# M3_SN755410_1_2.net
KiCad netlist of a schematic drawn in EAGLE
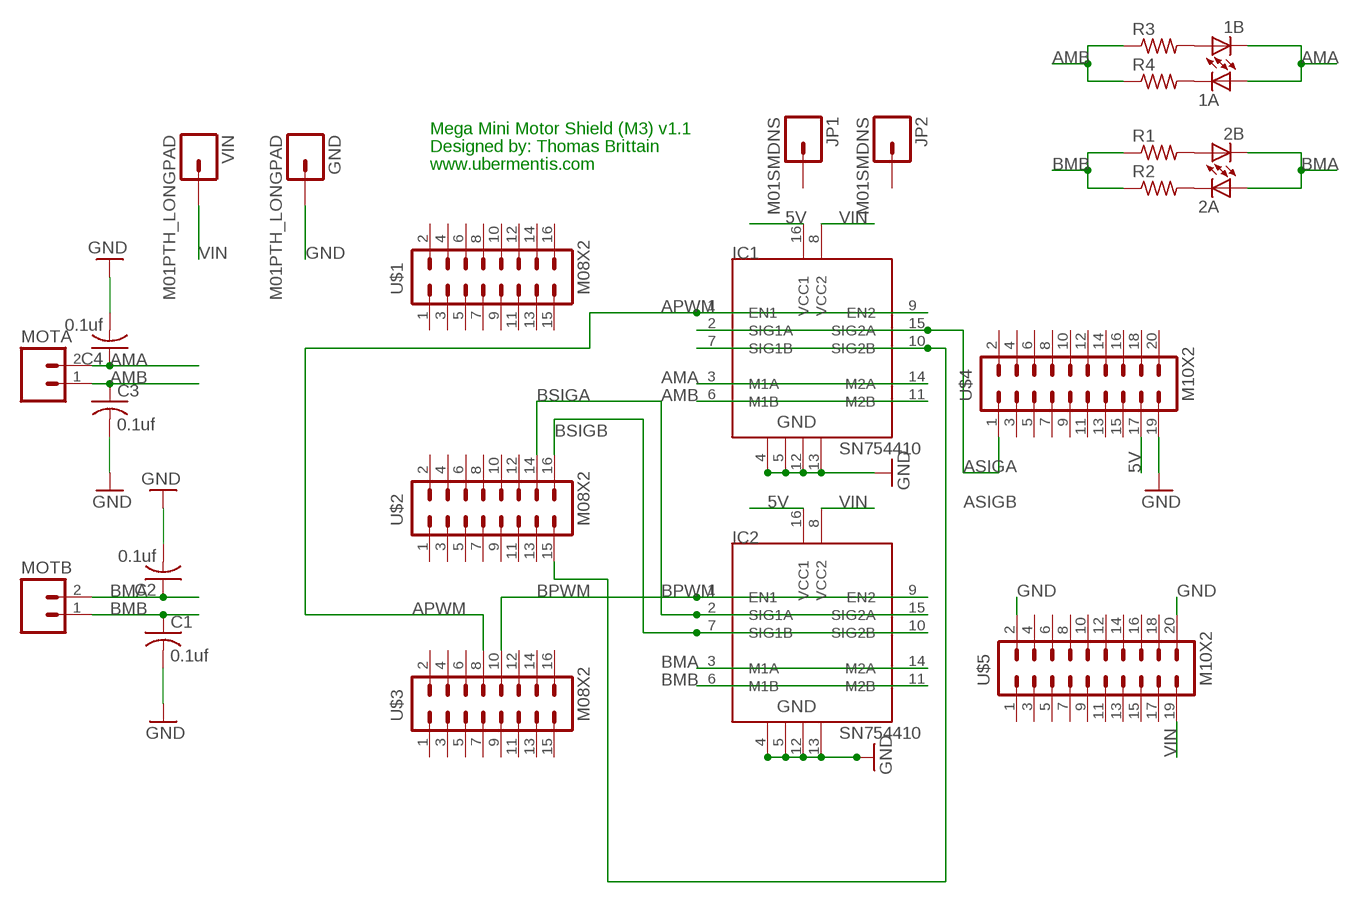
[diagram p0: schematic, sheet 1]

(export (version "E")
  (design (tool "Eeschema 10.0.6"))
  (components
    (comp (ref "1A")
      (value "LEDSML0603")
      (footprint "eagle-import:SML0603")
      (libsource (lib "eagle-import") (part "LEDSML0603"))
    )
    (comp (ref "1B")
      (value "LEDSML0603")
      (footprint "eagle-import:SML0603")
      (libsource (lib "eagle-import") (part "LEDSML0603"))
    )
    (comp (ref "2A")
      (value "LEDSML0603")
      (footprint "eagle-import:SML0603")
      (libsource (lib "eagle-import") (part "LEDSML0603"))
    )
    (comp (ref "2B")
      (value "LEDSML0603")
      (footprint "eagle-import:SML0603")
      (libsource (lib "eagle-import") (part "LEDSML0603"))
    )
    (comp (ref "C1")
      (value "0.1uf")
      (footprint "eagle-import:C0805")
      (libsource (lib "eagle-import") (part "C-USC0805"))
    )
    (comp (ref "C2")
      (value "0.1uf")
      (footprint "eagle-import:C0805")
      (libsource (lib "eagle-import") (part "C-USC0805"))
    )
    (comp (ref "C3")
      (value "0.1uf")
      (footprint "eagle-import:C0805")
      (libsource (lib "eagle-import") (part "C-USC0805"))
    )
    (comp (ref "C4")
      (value "0.1uf")
      (footprint "eagle-import:C0805")
      (libsource (lib "eagle-import") (part "C-USC0805"))
    )
    (comp (ref "GND")
      (value "M01PTH_LONGPAD")
      (footprint "eagle-import:1X01_LONGPAD")
      (libsource (lib "eagle-import") (part "M01PTH_LONGPAD"))
    )
    (comp (ref "IC1")
      (value "SN754410")
      (footprint "eagle-import:DIP16")
      (libsource (lib "eagle-import") (part "SN754410"))
    )
    (comp (ref "IC2")
      (value "SN754410")
      (footprint "eagle-import:DIP16")
      (libsource (lib "eagle-import") (part "SN754410"))
    )
    (comp (ref "JP1")
      (value "M01SMDNS")
      (footprint "eagle-import:1X01NS")
      (libsource (lib "eagle-import") (part "M01SMDNS"))
    )
    (comp (ref "JP2")
      (value "M01SMDNS")
      (footprint "eagle-import:1X01NS")
      (libsource (lib "eagle-import") (part "M01SMDNS"))
    )
    (comp (ref "MOTA")
      (value "M021X02_NO_SILK")
      (footprint "eagle-import:1X02_NO_SILK")
      (libsource (lib "eagle-import") (part "M021X02_NO_SILK"))
    )
    (comp (ref "MOTB")
      (value "M021X02_NO_SILK")
      (footprint "eagle-import:1X02_NO_SILK")
      (libsource (lib "eagle-import") (part "M021X02_NO_SILK"))
    )
    (comp (ref "R1")
      (value "R-US_R0805")
      (footprint "eagle-import:R0805")
      (libsource (lib "eagle-import") (part "R-US_R0805"))
    )
    (comp (ref "R2")
      (value "R-US_R0805")
      (footprint "eagle-import:R0805")
      (libsource (lib "eagle-import") (part "R-US_R0805"))
    )
    (comp (ref "R3")
      (value "R-US_R0805")
      (footprint "eagle-import:R0805")
      (libsource (lib "eagle-import") (part "R-US_R0805"))
    )
    (comp (ref "R4")
      (value "R-US_R0805")
      (footprint "eagle-import:R0805")
      (libsource (lib "eagle-import") (part "R-US_R0805"))
    )
    (comp (ref "U$1")
      (value "M08X2")
      (footprint "eagle-import:2X8")
      (libsource (lib "eagle-import") (part "M08X2"))
    )
    (comp (ref "U$2")
      (value "M08X2")
      (footprint "eagle-import:2X8")
      (libsource (lib "eagle-import") (part "M08X2"))
    )
    (comp (ref "U$3")
      (value "M08X2")
      (footprint "eagle-import:2X8")
      (libsource (lib "eagle-import") (part "M08X2"))
    )
    (comp (ref "U$4")
      (value "M10X2")
      (footprint "eagle-import:2X10")
      (libsource (lib "eagle-import") (part "M10X2"))
    )
    (comp (ref "U$5")
      (value "M10X2")
      (footprint "eagle-import:2X10")
      (libsource (lib "eagle-import") (part "M10X2"))
    )
    (comp (ref "VIN")
      (value "M01PTH_LONGPAD")
      (footprint "eagle-import:1X01_LONGPAD")
      (libsource (lib "eagle-import") (part "M01PTH_LONGPAD"))
    )
  )
  (nets
    (net (code "1") (name "/5V") (class "Default")
      (node (ref "IC1") (pin "16") (pinfunction "VCC1_16") (pintype "power_in"))
      (node (ref "IC2") (pin "16") (pinfunction "VCC1_16") (pintype "power_in"))
      (node (ref "U$4") (pin "17") (pinfunction "17_17") (pintype "passive"))
    )
    (net (code "2") (name "/AMA") (class "Default")
      (node (ref "1A") (pin "A") (pinfunction "A_A") (pintype "passive"))
      (node (ref "1B") (pin "C") (pinfunction "C_C") (pintype "passive"))
      (node (ref "C4") (pin "1") (pinfunction "1_1") (pintype "passive"))
      (node (ref "IC1") (pin "14") (pinfunction "M2A_14") (pintype "bidirectional"))
      (node (ref "IC1") (pin "3") (pinfunction "M1A_3") (pintype "bidirectional"))
      (node (ref "MOTA") (pin "2") (pinfunction "2_2") (pintype "passive"))
    )
    (net (code "3") (name "/AMB") (class "Default")
      (node (ref "C3") (pin "1") (pinfunction "1_1") (pintype "passive"))
      (node (ref "IC1") (pin "11") (pinfunction "M2B_11") (pintype "bidirectional"))
      (node (ref "IC1") (pin "6") (pinfunction "M1B_6") (pintype "bidirectional"))
      (node (ref "MOTA") (pin "1") (pinfunction "1_1") (pintype "passive"))
      (node (ref "R3") (pin "1") (pinfunction "1_1") (pintype "passive"))
      (node (ref "R4") (pin "1") (pinfunction "1_1") (pintype "passive"))
    )
    (net (code "4") (name "/APWM") (class "Default")
      (node (ref "IC1") (pin "1") (pinfunction "EN1_1") (pintype "bidirectional"))
      (node (ref "IC1") (pin "9") (pinfunction "EN2_9") (pintype "bidirectional"))
      (node (ref "U$3") (pin "8") (pinfunction "8_8") (pintype "passive"))
    )
    (net (code "5") (name "/ASIGA") (class "Default")
      (node (ref "IC1") (pin "15") (pinfunction "SIG2A_15") (pintype "bidirectional"))
      (node (ref "IC1") (pin "2") (pinfunction "SIG1A_2") (pintype "bidirectional"))
      (node (ref "U$4") (pin "1") (pinfunction "1_1") (pintype "passive"))
    )
    (net (code "6") (name "/ASIGB") (class "Default")
      (node (ref "IC1") (pin "10") (pinfunction "SIG2B_10") (pintype "bidirectional"))
      (node (ref "IC1") (pin "7") (pinfunction "SIG1B_7") (pintype "bidirectional"))
      (node (ref "U$2") (pin "15") (pinfunction "15_15") (pintype "passive"))
    )
    (net (code "7") (name "/BMA") (class "Default")
      (node (ref "2A") (pin "A") (pinfunction "A_A") (pintype "passive"))
      (node (ref "2B") (pin "C") (pinfunction "C_C") (pintype "passive"))
      (node (ref "C2") (pin "1") (pinfunction "1_1") (pintype "passive"))
      (node (ref "IC2") (pin "14") (pinfunction "M2A_14") (pintype "bidirectional"))
      (node (ref "IC2") (pin "3") (pinfunction "M1A_3") (pintype "bidirectional"))
      (node (ref "MOTB") (pin "2") (pinfunction "2_2") (pintype "passive"))
    )
    (net (code "8") (name "/BMB") (class "Default")
      (node (ref "C1") (pin "1") (pinfunction "1_1") (pintype "passive"))
      (node (ref "IC2") (pin "11") (pinfunction "M2B_11") (pintype "bidirectional"))
      (node (ref "IC2") (pin "6") (pinfunction "M1B_6") (pintype "bidirectional"))
      (node (ref "MOTB") (pin "1") (pinfunction "1_1") (pintype "passive"))
      (node (ref "R1") (pin "1") (pinfunction "1_1") (pintype "passive"))
      (node (ref "R2") (pin "1") (pinfunction "1_1") (pintype "passive"))
    )
    (net (code "9") (name "/BPWM") (class "Default")
      (node (ref "IC2") (pin "1") (pinfunction "EN1_1") (pintype "bidirectional"))
      (node (ref "IC2") (pin "9") (pinfunction "EN2_9") (pintype "bidirectional"))
      (node (ref "U$3") (pin "10") (pinfunction "10_10") (pintype "passive"))
    )
    (net (code "10") (name "/BSIGA") (class "Default")
      (node (ref "IC2") (pin "15") (pinfunction "SIG2A_15") (pintype "bidirectional"))
      (node (ref "IC2") (pin "2") (pinfunction "SIG1A_2") (pintype "bidirectional"))
      (node (ref "U$2") (pin "14") (pinfunction "14_14") (pintype "passive"))
    )
    (net (code "11") (name "/BSIGB") (class "Default")
      (node (ref "IC2") (pin "10") (pinfunction "SIG2B_10") (pintype "bidirectional"))
      (node (ref "IC2") (pin "7") (pinfunction "SIG1B_7") (pintype "bidirectional"))
      (node (ref "U$2") (pin "16") (pinfunction "16_16") (pintype "passive"))
    )
    (net (code "12") (name "/VIN") (class "Default")
      (node (ref "IC1") (pin "8") (pinfunction "VCC2_8") (pintype "power_in"))
      (node (ref "IC2") (pin "8") (pinfunction "VCC2_8") (pintype "power_in"))
      (node (ref "U$5") (pin "19") (pinfunction "19_19") (pintype "passive"))
      (node (ref "VIN") (pin "1") (pinfunction "1_1") (pintype "passive"))
    )
    (net (code "13") (name "GND") (class "Default")
      (node (ref "C1") (pin "2") (pinfunction "2_2") (pintype "passive"))
      (node (ref "C2") (pin "2") (pinfunction "2_2") (pintype "passive"))
      (node (ref "C3") (pin "2") (pinfunction "2_2") (pintype "passive"))
      (node (ref "C4") (pin "2") (pinfunction "2_2") (pintype "passive"))
      (node (ref "GND") (pin "1") (pinfunction "1_1") (pintype "passive"))
      (node (ref "IC1") (pin "12") (pinfunction "P12_12") (pintype "power_in"))
      (node (ref "IC1") (pin "13") (pinfunction "P13_13") (pintype "power_in"))
      (node (ref "IC1") (pin "4") (pinfunction "P4_4") (pintype "power_in"))
      (node (ref "IC1") (pin "5") (pinfunction "P5_5") (pintype "power_in"))
      (node (ref "IC2") (pin "12") (pinfunction "P12_12") (pintype "power_in"))
      (node (ref "IC2") (pin "13") (pinfunction "P13_13") (pintype "power_in"))
      (node (ref "IC2") (pin "4") (pinfunction "P4_4") (pintype "power_in"))
      (node (ref "IC2") (pin "5") (pinfunction "P5_5") (pintype "power_in"))
      (node (ref "U$4") (pin "19") (pinfunction "19_19") (pintype "passive"))
      (node (ref "U$5") (pin "2") (pinfunction "2_2") (pintype "passive"))
      (node (ref "U$5") (pin "20") (pinfunction "20_20") (pintype "passive"))
    )
    (net (code "14") (name "Net-(1A-PadC)") (class "Default")
      (node (ref "1A") (pin "C") (pinfunction "C_C") (pintype "passive"))
      (node (ref "R4") (pin "2") (pinfunction "2_2") (pintype "passive"))
    )
    (net (code "15") (name "Net-(1B-PadA)") (class "Default")
      (node (ref "1B") (pin "A") (pinfunction "A_A") (pintype "passive"))
      (node (ref "R3") (pin "2") (pinfunction "2_2") (pintype "passive"))
    )
    (net (code "16") (name "Net-(2A-PadC)") (class "Default")
      (node (ref "2A") (pin "C") (pinfunction "C_C") (pintype "passive"))
      (node (ref "R2") (pin "2") (pinfunction "2_2") (pintype "passive"))
    )
    (net (code "17") (name "Net-(2B-PadA)") (class "Default")
      (node (ref "2B") (pin "A") (pinfunction "A_A") (pintype "passive"))
      (node (ref "R1") (pin "2") (pinfunction "2_2") (pintype "passive"))
    )
    (net (code "18") (name "unconnected-(JP1-Pad1)") (class "Default")
      (node (ref "JP1") (pin "1") (pinfunction "1_1") (pintype "passive"))
    )
    (net (code "19") (name "unconnected-(JP2-Pad1)") (class "Default")
      (node (ref "JP2") (pin "1") (pinfunction "1_1") (pintype "passive"))
    )
    (net (code "20") (name "unconnected-(U$1-Pad1)") (class "Default")
      (node (ref "U$1") (pin "1") (pinfunction "1_1") (pintype "passive"))
    )
    (net (code "21") (name "unconnected-(U$1-Pad2)") (class "Default")
      (node (ref "U$1") (pin "2") (pinfunction "2_2") (pintype "passive"))
    )
    (net (code "22") (name "unconnected-(U$1-Pad3)") (class "Default")
      (node (ref "U$1") (pin "3") (pinfunction "3_3") (pintype "passive"))
    )
    (net (code "23") (name "unconnected-(U$1-Pad4)") (class "Default")
      (node (ref "U$1") (pin "4") (pinfunction "4_4") (pintype "passive"))
    )
    (net (code "24") (name "unconnected-(U$1-Pad5)") (class "Default")
      (node (ref "U$1") (pin "5") (pinfunction "5_5") (pintype "passive"))
    )
    (net (code "25") (name "unconnected-(U$1-Pad6)") (class "Default")
      (node (ref "U$1") (pin "6") (pinfunction "6_6") (pintype "passive"))
    )
    (net (code "26") (name "unconnected-(U$1-Pad7)") (class "Default")
      (node (ref "U$1") (pin "7") (pinfunction "7_7") (pintype "passive"))
    )
    (net (code "27") (name "unconnected-(U$1-Pad8)") (class "Default")
      (node (ref "U$1") (pin "8") (pinfunction "8_8") (pintype "passive"))
    )
    (net (code "28") (name "unconnected-(U$1-Pad9)") (class "Default")
      (node (ref "U$1") (pin "9") (pinfunction "9_9") (pintype "passive"))
    )
    (net (code "29") (name "unconnected-(U$1-Pad10)") (class "Default")
      (node (ref "U$1") (pin "10") (pinfunction "10_10") (pintype "passive"))
    )
    (net (code "30") (name "unconnected-(U$1-Pad11)") (class "Default")
      (node (ref "U$1") (pin "11") (pinfunction "11_11") (pintype "passive"))
    )
    (net (code "31") (name "unconnected-(U$1-Pad12)") (class "Default")
      (node (ref "U$1") (pin "12") (pinfunction "12_12") (pintype "passive"))
    )
    (net (code "32") (name "unconnected-(U$1-Pad13)") (class "Default")
      (node (ref "U$1") (pin "13") (pinfunction "13_13") (pintype "passive"))
    )
    (net (code "33") (name "unconnected-(U$1-Pad14)") (class "Default")
      (node (ref "U$1") (pin "14") (pinfunction "14_14") (pintype "passive"))
    )
    (net (code "34") (name "unconnected-(U$1-Pad15)") (class "Default")
      (node (ref "U$1") (pin "15") (pinfunction "15_15") (pintype "passive"))
    )
    (net (code "35") (name "unconnected-(U$1-Pad16)") (class "Default")
      (node (ref "U$1") (pin "16") (pinfunction "16_16") (pintype "passive"))
    )
    (net (code "36") (name "unconnected-(U$2-Pad1)") (class "Default")
      (node (ref "U$2") (pin "1") (pinfunction "1_1") (pintype "passive"))
    )
    (net (code "37") (name "unconnected-(U$2-Pad2)") (class "Default")
      (node (ref "U$2") (pin "2") (pinfunction "2_2") (pintype "passive"))
    )
    (net (code "38") (name "unconnected-(U$2-Pad3)") (class "Default")
      (node (ref "U$2") (pin "3") (pinfunction "3_3") (pintype "passive"))
    )
    (net (code "39") (name "unconnected-(U$2-Pad4)") (class "Default")
      (node (ref "U$2") (pin "4") (pinfunction "4_4") (pintype "passive"))
    )
    (net (code "40") (name "unconnected-(U$2-Pad5)") (class "Default")
      (node (ref "U$2") (pin "5") (pinfunction "5_5") (pintype "passive"))
    )
    (net (code "41") (name "unconnected-(U$2-Pad6)") (class "Default")
      (node (ref "U$2") (pin "6") (pinfunction "6_6") (pintype "passive"))
    )
    (net (code "42") (name "unconnected-(U$2-Pad7)") (class "Default")
      (node (ref "U$2") (pin "7") (pinfunction "7_7") (pintype "passive"))
    )
    (net (code "43") (name "unconnected-(U$2-Pad8)") (class "Default")
      (node (ref "U$2") (pin "8") (pinfunction "8_8") (pintype "passive"))
    )
    (net (code "44") (name "unconnected-(U$2-Pad9)") (class "Default")
      (node (ref "U$2") (pin "9") (pinfunction "9_9") (pintype "passive"))
    )
    (net (code "45") (name "unconnected-(U$2-Pad10)") (class "Default")
      (node (ref "U$2") (pin "10") (pinfunction "10_10") (pintype "passive"))
    )
    (net (code "46") (name "unconnected-(U$2-Pad11)") (class "Default")
      (node (ref "U$2") (pin "11") (pinfunction "11_11") (pintype "passive"))
    )
    (net (code "47") (name "unconnected-(U$2-Pad12)") (class "Default")
      (node (ref "U$2") (pin "12") (pinfunction "12_12") (pintype "passive"))
    )
    (net (code "48") (name "unconnected-(U$2-Pad13)") (class "Default")
      (node (ref "U$2") (pin "13") (pinfunction "13_13") (pintype "passive"))
    )
    (net (code "49") (name "unconnected-(U$3-Pad1)") (class "Default")
      (node (ref "U$3") (pin "1") (pinfunction "1_1") (pintype "passive"))
    )
    (net (code "50") (name "unconnected-(U$3-Pad2)") (class "Default")
      (node (ref "U$3") (pin "2") (pinfunction "2_2") (pintype "passive"))
    )
    (net (code "51") (name "unconnected-(U$3-Pad3)") (class "Default")
      (node (ref "U$3") (pin "3") (pinfunction "3_3") (pintype "passive"))
    )
    (net (code "52") (name "unconnected-(U$3-Pad4)") (class "Default")
      (node (ref "U$3") (pin "4") (pinfunction "4_4") (pintype "passive"))
    )
    (net (code "53") (name "unconnected-(U$3-Pad5)") (class "Default")
      (node (ref "U$3") (pin "5") (pinfunction "5_5") (pintype "passive"))
    )
    (net (code "54") (name "unconnected-(U$3-Pad6)") (class "Default")
      (node (ref "U$3") (pin "6") (pinfunction "6_6") (pintype "passive"))
    )
    (net (code "55") (name "unconnected-(U$3-Pad7)") (class "Default")
      (node (ref "U$3") (pin "7") (pinfunction "7_7") (pintype "passive"))
    )
    (net (code "56") (name "unconnected-(U$3-Pad9)") (class "Default")
      (node (ref "U$3") (pin "9") (pinfunction "9_9") (pintype "passive"))
    )
    (net (code "57") (name "unconnected-(U$3-Pad11)") (class "Default")
      (node (ref "U$3") (pin "11") (pinfunction "11_11") (pintype "passive"))
    )
    (net (code "58") (name "unconnected-(U$3-Pad12)") (class "Default")
      (node (ref "U$3") (pin "12") (pinfunction "12_12") (pintype "passive"))
    )
    (net (code "59") (name "unconnected-(U$3-Pad13)") (class "Default")
      (node (ref "U$3") (pin "13") (pinfunction "13_13") (pintype "passive"))
    )
    (net (code "60") (name "unconnected-(U$3-Pad14)") (class "Default")
      (node (ref "U$3") (pin "14") (pinfunction "14_14") (pintype "passive"))
    )
    (net (code "61") (name "unconnected-(U$3-Pad15)") (class "Default")
      (node (ref "U$3") (pin "15") (pinfunction "15_15") (pintype "passive"))
    )
    (net (code "62") (name "unconnected-(U$3-Pad16)") (class "Default")
      (node (ref "U$3") (pin "16") (pinfunction "16_16") (pintype "passive"))
    )
    (net (code "63") (name "unconnected-(U$4-Pad2)") (class "Default")
      (node (ref "U$4") (pin "2") (pinfunction "2_2") (pintype "passive"))
    )
    (net (code "64") (name "unconnected-(U$4-Pad3)") (class "Default")
      (node (ref "U$4") (pin "3") (pinfunction "3_3") (pintype "passive"))
    )
    (net (code "65") (name "unconnected-(U$4-Pad4)") (class "Default")
      (node (ref "U$4") (pin "4") (pinfunction "4_4") (pintype "passive"))
    )
    (net (code "66") (name "unconnected-(U$4-Pad5)") (class "Default")
      (node (ref "U$4") (pin "5") (pinfunction "5_5") (pintype "passive"))
    )
    (net (code "67") (name "unconnected-(U$4-Pad6)") (class "Default")
      (node (ref "U$4") (pin "6") (pinfunction "6_6") (pintype "passive"))
    )
    (net (code "68") (name "unconnected-(U$4-Pad7)") (class "Default")
      (node (ref "U$4") (pin "7") (pinfunction "7_7") (pintype "passive"))
    )
    (net (code "69") (name "unconnected-(U$4-Pad8)") (class "Default")
      (node (ref "U$4") (pin "8") (pinfunction "8_8") (pintype "passive"))
    )
    (net (code "70") (name "unconnected-(U$4-Pad9)") (class "Default")
      (node (ref "U$4") (pin "9") (pinfunction "9_9") (pintype "passive"))
    )
    (net (code "71") (name "unconnected-(U$4-Pad10)") (class "Default")
      (node (ref "U$4") (pin "10") (pinfunction "10_10") (pintype "passive"))
    )
    (net (code "72") (name "unconnected-(U$4-Pad11)") (class "Default")
      (node (ref "U$4") (pin "11") (pinfunction "11_11") (pintype "passive"))
    )
    (net (code "73") (name "unconnected-(U$4-Pad12)") (class "Default")
      (node (ref "U$4") (pin "12") (pinfunction "12_12") (pintype "passive"))
    )
    (net (code "74") (name "unconnected-(U$4-Pad13)") (class "Default")
      (node (ref "U$4") (pin "13") (pinfunction "13_13") (pintype "passive"))
    )
    (net (code "75") (name "unconnected-(U$4-Pad14)") (class "Default")
      (node (ref "U$4") (pin "14") (pinfunction "14_14") (pintype "passive"))
    )
    (net (code "76") (name "unconnected-(U$4-Pad15)") (class "Default")
      (node (ref "U$4") (pin "15") (pinfunction "15_15") (pintype "passive"))
    )
    (net (code "77") (name "unconnected-(U$4-Pad16)") (class "Default")
      (node (ref "U$4") (pin "16") (pinfunction "16_16") (pintype "passive"))
    )
    (net (code "78") (name "unconnected-(U$4-Pad18)") (class "Default")
      (node (ref "U$4") (pin "18") (pinfunction "18_18") (pintype "passive"))
    )
    (net (code "79") (name "unconnected-(U$4-Pad20)") (class "Default")
      (node (ref "U$4") (pin "20") (pinfunction "20_20") (pintype "passive"))
    )
    (net (code "80") (name "unconnected-(U$5-Pad1)") (class "Default")
      (node (ref "U$5") (pin "1") (pinfunction "1_1") (pintype "passive"))
    )
    (net (code "81") (name "unconnected-(U$5-Pad3)") (class "Default")
      (node (ref "U$5") (pin "3") (pinfunction "3_3") (pintype "passive"))
    )
    (net (code "82") (name "unconnected-(U$5-Pad4)") (class "Default")
      (node (ref "U$5") (pin "4") (pinfunction "4_4") (pintype "passive"))
    )
    (net (code "83") (name "unconnected-(U$5-Pad5)") (class "Default")
      (node (ref "U$5") (pin "5") (pinfunction "5_5") (pintype "passive"))
    )
    (net (code "84") (name "unconnected-(U$5-Pad6)") (class "Default")
      (node (ref "U$5") (pin "6") (pinfunction "6_6") (pintype "passive"))
    )
    (net (code "85") (name "unconnected-(U$5-Pad7)") (class "Default")
      (node (ref "U$5") (pin "7") (pinfunction "7_7") (pintype "passive"))
    )
    (net (code "86") (name "unconnected-(U$5-Pad8)") (class "Default")
      (node (ref "U$5") (pin "8") (pinfunction "8_8") (pintype "passive"))
    )
    (net (code "87") (name "unconnected-(U$5-Pad9)") (class "Default")
      (node (ref "U$5") (pin "9") (pinfunction "9_9") (pintype "passive"))
    )
    (net (code "88") (name "unconnected-(U$5-Pad10)") (class "Default")
      (node (ref "U$5") (pin "10") (pinfunction "10_10") (pintype "passive"))
    )
    (net (code "89") (name "unconnected-(U$5-Pad11)") (class "Default")
      (node (ref "U$5") (pin "11") (pinfunction "11_11") (pintype "passive"))
    )
    (net (code "90") (name "unconnected-(U$5-Pad12)") (class "Default")
      (node (ref "U$5") (pin "12") (pinfunction "12_12") (pintype "passive"))
    )
    (net (code "91") (name "unconnected-(U$5-Pad13)") (class "Default")
      (node (ref "U$5") (pin "13") (pinfunction "13_13") (pintype "passive"))
    )
    (net (code "92") (name "unconnected-(U$5-Pad14)") (class "Default")
      (node (ref "U$5") (pin "14") (pinfunction "14_14") (pintype "passive"))
    )
    (net (code "93") (name "unconnected-(U$5-Pad15)") (class "Default")
      (node (ref "U$5") (pin "15") (pinfunction "15_15") (pintype "passive"))
    )
    (net (code "94") (name "unconnected-(U$5-Pad16)") (class "Default")
      (node (ref "U$5") (pin "16") (pinfunction "16_16") (pintype "passive"))
    )
    (net (code "95") (name "unconnected-(U$5-Pad17)") (class "Default")
      (node (ref "U$5") (pin "17") (pinfunction "17_17") (pintype "passive"))
    )
    (net (code "96") (name "unconnected-(U$5-Pad18)") (class "Default")
      (node (ref "U$5") (pin "18") (pinfunction "18_18") (pintype "passive"))
    )
  )
)
